# Hermes_v1.net
KiCad netlist of a schematic drawn in EAGLE
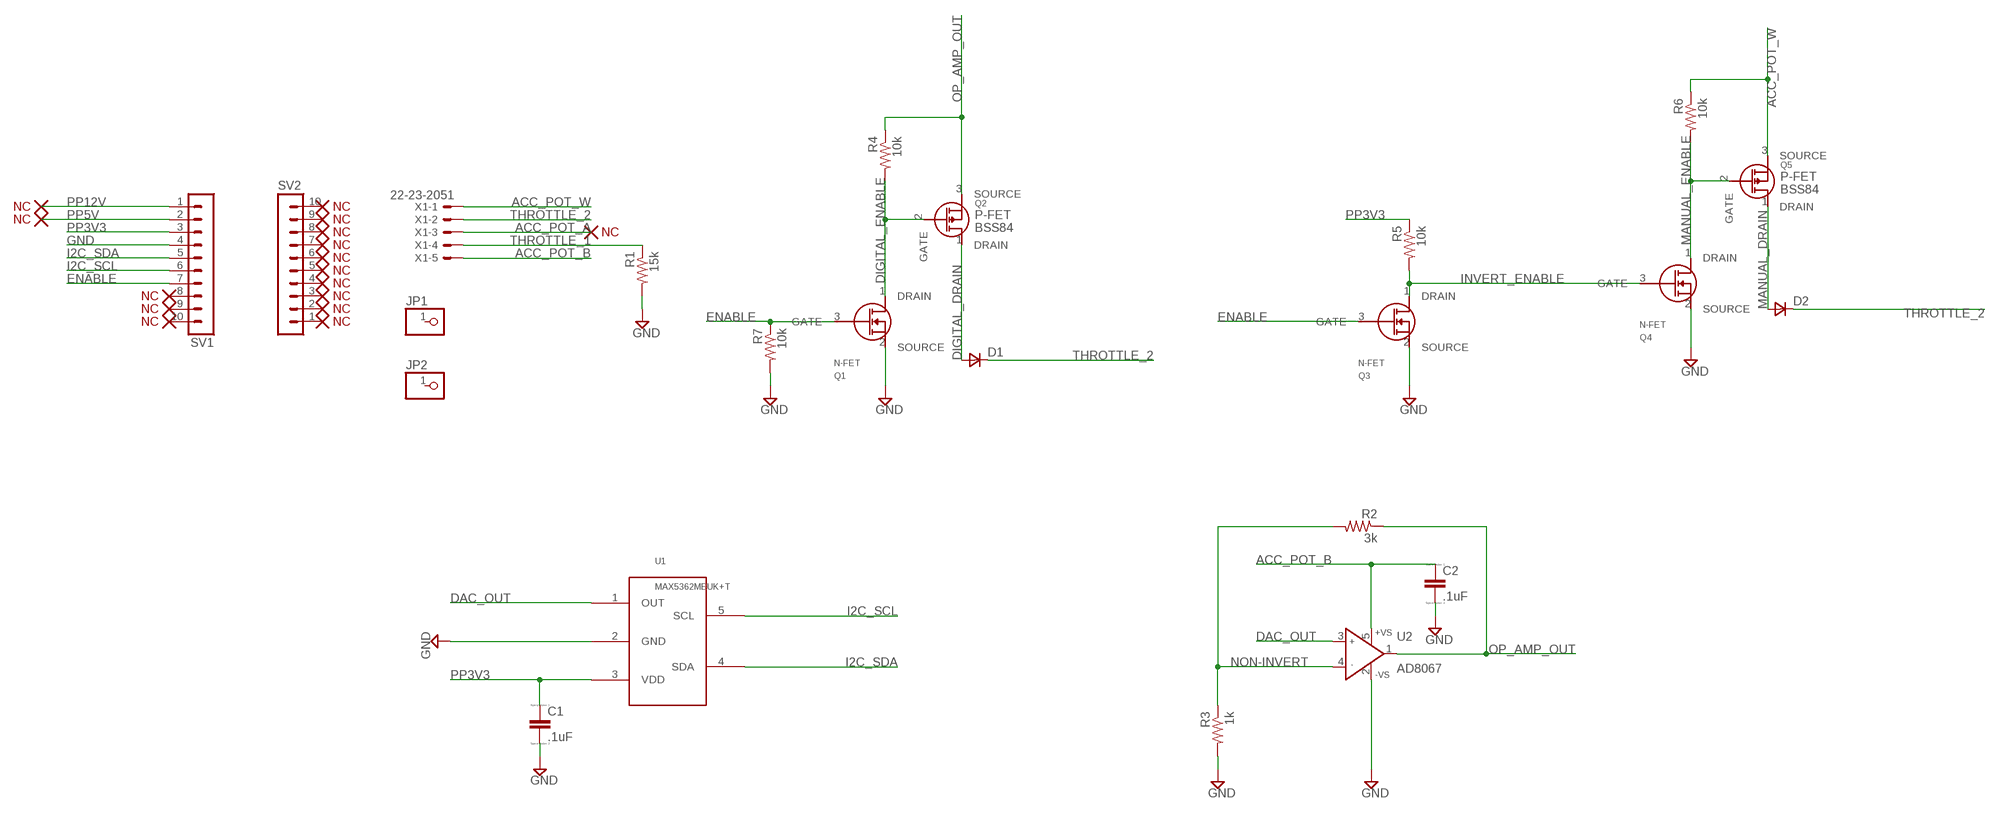
[diagram p0: schematic, sheet 1]

(export (version "E")
  (design (tool "Eeschema 10.0.6"))
  (components
    (comp (ref "C1")
      (value ".1uF")
      (footprint "eagle-import:C0402")
      (libsource (lib "eagle-import") (part "CC0402"))
    )
    (comp (ref "C2")
      (value ".1uF")
      (footprint "eagle-import:C0402")
      (libsource (lib "eagle-import") (part "CC0402"))
    )
    (comp (ref "D1")
      (value "DSOD323")
      (footprint "eagle-import:SOD323")
      (fields (field (name "MPN") "CDSOD323-T05C"))
      (libsource (lib "eagle-import") (part "DSOD323"))
    )
    (comp (ref "D2")
      (value "DSOD323")
      (footprint "eagle-import:SOD323")
      (fields (field (name "MPN") "CDSOD323-T05C"))
      (libsource (lib "eagle-import") (part "DSOD323"))
    )
    (comp (ref "JP1")
      (value "PINHD-1X1")
      (footprint "eagle-import:1X01")
      (libsource (lib "eagle-import") (part "PINHD-1X1"))
    )
    (comp (ref "JP2")
      (value "PINHD-1X1")
      (footprint "eagle-import:1X01")
      (libsource (lib "eagle-import") (part "PINHD-1X1"))
    )
    (comp (ref "Q1")
      (value "NMOSFET")
      (footprint "eagle-import:SOT-23")
      (libsource (lib "eagle-import") (part "NMOSFET"))
    )
    (comp (ref "Q2")
      (value "P-FET")
      (footprint "eagle-import:SOT-23")
      (libsource (lib "eagle-import") (part "P-FET"))
    )
    (comp (ref "Q3")
      (value "NMOSFET")
      (footprint "eagle-import:SOT-23")
      (libsource (lib "eagle-import") (part "NMOSFET"))
    )
    (comp (ref "Q4")
      (value "NMOSFET")
      (footprint "eagle-import:SOT-23")
      (libsource (lib "eagle-import") (part "NMOSFET"))
    )
    (comp (ref "Q5")
      (value "P-FET")
      (footprint "eagle-import:SOT-23")
      (libsource (lib "eagle-import") (part "P-FET"))
    )
    (comp (ref "R1")
      (value "15k")
      (footprint "eagle-import:R0603")
      (libsource (lib "eagle-import") (part "R-US_R0603"))
    )
    (comp (ref "R2")
      (value "3k")
      (footprint "eagle-import:R0603")
      (libsource (lib "eagle-import") (part "R-US_R0603"))
    )
    (comp (ref "R3")
      (value "1k")
      (footprint "eagle-import:R0603")
      (libsource (lib "eagle-import") (part "R-US_R0603"))
    )
    (comp (ref "R4")
      (value "10k")
      (footprint "eagle-import:R0603")
      (libsource (lib "eagle-import") (part "R-US_R0603"))
    )
    (comp (ref "R5")
      (value "10k")
      (footprint "eagle-import:R0603")
      (libsource (lib "eagle-import") (part "R-US_R0603"))
    )
    (comp (ref "R6")
      (value "10k")
      (footprint "eagle-import:R0603")
      (libsource (lib "eagle-import") (part "R-US_R0603"))
    )
    (comp (ref "R7")
      (value "10k")
      (footprint "eagle-import:R0603")
      (libsource (lib "eagle-import") (part "R-US_R0603"))
    )
    (comp (ref "SV1")
      (value "MA10-1")
      (footprint "eagle-import:MA10-1")
      (libsource (lib "eagle-import") (part "MA10-1"))
    )
    (comp (ref "SV2")
      (value "MA10-1")
      (footprint "eagle-import:MA10-1")
      (libsource (lib "eagle-import") (part "MA10-1"))
    )
    (comp (ref "U1")
      (value "DAC")
      (footprint "eagle-import:SOT23-5")
      (libsource (lib "eagle-import") (part "DAC"))
    )
    (comp (ref "U2")
      (value "AD8067")
      (footprint "eagle-import:SOT23-5")
      (fields (field (name "MF") "ALTERA CORPORATION") (field (name "MPN") "AD8067ARTZ-REEL7"))
      (libsource (lib "eagle-import") (part "AD8067"))
    )
    (comp (ref "X1")
      (value "22-23-2051")
      (footprint "eagle-import:22-23-2051")
      (fields (field (name "MF") "MOLEX"))
      (libsource (lib "eagle-import") (part "22-23-2051"))
    )
  )
  (nets
    (net (code "1") (name "/ACC_POT_A") (class "Default")
      (node (ref "X1") (pin "3") (pinfunction "S_3") (pintype "passive"))
    )
    (net (code "2") (name "/ACC_POT_B") (class "Default")
      (node (ref "C2") (pin "1") (pinfunction "1_1") (pintype "passive"))
      (node (ref "U2") (pin "5") (pinfunction "+VS_5") (pintype "input"))
      (node (ref "X1") (pin "5") (pinfunction "S_5") (pintype "passive"))
    )
    (net (code "3") (name "/ACC_POT_W") (class "Default")
      (node (ref "Q5") (pin "3") (pinfunction "SOURCE_3") (pintype "bidirectional"))
      (node (ref "R6") (pin "1") (pinfunction "1_1") (pintype "passive"))
      (node (ref "X1") (pin "1") (pinfunction "S_1") (pintype "passive"))
    )
    (net (code "4") (name "/DAC_OUT") (class "Default")
      (node (ref "U1") (pin "1") (pinfunction "OUT_1") (pintype "bidirectional"))
      (node (ref "U2") (pin "3") (pinfunction "IN+_3") (pintype "input"))
    )
    (net (code "5") (name "/DIGITAL_DRAIN") (class "Default")
      (node (ref "D1") (pin "2") (pinfunction "A_2") (pintype "passive"))
      (node (ref "Q2") (pin "1") (pinfunction "DRAIN_1") (pintype "bidirectional"))
    )
    (net (code "6") (name "/DIGITAL_ENABLE") (class "Default")
      (node (ref "Q1") (pin "1") (pinfunction "DRAIN_1") (pintype "bidirectional"))
      (node (ref "Q2") (pin "2") (pinfunction "GATE_2") (pintype "bidirectional"))
      (node (ref "R4") (pin "2") (pinfunction "2_2") (pintype "passive"))
    )
    (net (code "7") (name "/ENABLE") (class "Default")
      (node (ref "Q1") (pin "3") (pinfunction "GATE_3") (pintype "bidirectional"))
      (node (ref "Q3") (pin "3") (pinfunction "GATE_3") (pintype "bidirectional"))
      (node (ref "R7") (pin "1") (pinfunction "1_1") (pintype "passive"))
      (node (ref "SV1") (pin "7") (pinfunction "7_7") (pintype "passive"))
    )
    (net (code "8") (name "/I2C_SCL") (class "Default")
      (node (ref "SV1") (pin "6") (pinfunction "6_6") (pintype "passive"))
      (node (ref "U1") (pin "5") (pinfunction "SCL_5") (pintype "bidirectional"))
    )
    (net (code "9") (name "/I2C_SDA") (class "Default")
      (node (ref "SV1") (pin "5") (pinfunction "5_5") (pintype "passive"))
      (node (ref "U1") (pin "4") (pinfunction "SDA_4") (pintype "bidirectional"))
    )
    (net (code "10") (name "/INVERT_ENABLE") (class "Default")
      (node (ref "Q3") (pin "1") (pinfunction "DRAIN_1") (pintype "bidirectional"))
      (node (ref "Q4") (pin "3") (pinfunction "GATE_3") (pintype "bidirectional"))
      (node (ref "R5") (pin "2") (pinfunction "2_2") (pintype "passive"))
    )
    (net (code "11") (name "/MANUAL_DRAIN") (class "Default")
      (node (ref "D2") (pin "2") (pinfunction "A_2") (pintype "passive"))
      (node (ref "Q5") (pin "1") (pinfunction "DRAIN_1") (pintype "bidirectional"))
    )
    (net (code "12") (name "/MANUAL_ENABLE") (class "Default")
      (node (ref "Q4") (pin "1") (pinfunction "DRAIN_1") (pintype "bidirectional"))
      (node (ref "Q5") (pin "2") (pinfunction "GATE_2") (pintype "bidirectional"))
      (node (ref "R6") (pin "2") (pinfunction "2_2") (pintype "passive"))
    )
    (net (code "13") (name "/NON-INVERT") (class "Default")
      (node (ref "R2") (pin "2") (pinfunction "2_2") (pintype "passive"))
      (node (ref "R3") (pin "1") (pinfunction "1_1") (pintype "passive"))
      (node (ref "U2") (pin "4") (pinfunction "IN-_4") (pintype "input"))
    )
    (net (code "14") (name "/OP_AMP_OUT") (class "Default")
      (node (ref "Q2") (pin "3") (pinfunction "SOURCE_3") (pintype "bidirectional"))
      (node (ref "R2") (pin "1") (pinfunction "1_1") (pintype "passive"))
      (node (ref "R4") (pin "1") (pinfunction "1_1") (pintype "passive"))
      (node (ref "U2") (pin "1") (pinfunction "OUT_1") (pintype "output"))
    )
    (net (code "15") (name "/PP3V3") (class "Default")
      (node (ref "C1") (pin "1") (pinfunction "1_1") (pintype "passive"))
      (node (ref "R5") (pin "1") (pinfunction "1_1") (pintype "passive"))
      (node (ref "SV1") (pin "3") (pinfunction "3_3") (pintype "passive"))
      (node (ref "U1") (pin "3") (pinfunction "VDD_3") (pintype "bidirectional"))
    )
    (net (code "16") (name "/PP5V") (class "Default")
      (node (ref "SV1") (pin "2") (pinfunction "2_2") (pintype "passive"))
    )
    (net (code "17") (name "/PP12V") (class "Default")
      (node (ref "SV1") (pin "1") (pinfunction "1_1") (pintype "passive"))
    )
    (net (code "18") (name "/THROTTLE_1") (class "Default")
      (node (ref "R1") (pin "1") (pinfunction "1_1") (pintype "passive"))
      (node (ref "X1") (pin "4") (pinfunction "S_4") (pintype "passive"))
    )
    (net (code "19") (name "/THROTTLE_2") (class "Default")
      (node (ref "D1") (pin "1") (pinfunction "C_1") (pintype "passive"))
      (node (ref "D2") (pin "1") (pinfunction "C_1") (pintype "passive"))
      (node (ref "X1") (pin "2") (pinfunction "S_2") (pintype "passive"))
    )
    (net (code "20") (name "GND") (class "Default")
      (node (ref "C1") (pin "2") (pinfunction "2_2") (pintype "passive"))
      (node (ref "C2") (pin "2") (pinfunction "2_2") (pintype "passive"))
      (node (ref "Q1") (pin "2") (pinfunction "SOURCE_2") (pintype "bidirectional"))
      (node (ref "Q3") (pin "2") (pinfunction "SOURCE_2") (pintype "bidirectional"))
      (node (ref "Q4") (pin "2") (pinfunction "SOURCE_2") (pintype "bidirectional"))
      (node (ref "R1") (pin "2") (pinfunction "2_2") (pintype "passive"))
      (node (ref "R3") (pin "2") (pinfunction "2_2") (pintype "passive"))
      (node (ref "R7") (pin "2") (pinfunction "2_2") (pintype "passive"))
      (node (ref "SV1") (pin "4") (pinfunction "4_4") (pintype "passive"))
      (node (ref "U1") (pin "2") (pinfunction "GND_2") (pintype "bidirectional"))
      (node (ref "U2") (pin "2") (pinfunction "-VS_2") (pintype "input"))
    )
    (net (code "21") (name "unconnected-(JP1-Pad1)") (class "Default")
      (node (ref "JP1") (pin "1") (pinfunction "1_1") (pintype "passive"))
    )
    (net (code "22") (name "unconnected-(JP2-Pad1)") (class "Default")
      (node (ref "JP2") (pin "1") (pinfunction "1_1") (pintype "passive"))
    )
    (net (code "23") (name "unconnected-(SV1-Pad8)") (class "Default")
      (node (ref "SV1") (pin "8") (pinfunction "8_8") (pintype "passive"))
    )
    (net (code "24") (name "unconnected-(SV1-Pad9)") (class "Default")
      (node (ref "SV1") (pin "9") (pinfunction "9_9") (pintype "passive"))
    )
    (net (code "25") (name "unconnected-(SV1-Pad10)") (class "Default")
      (node (ref "SV1") (pin "10") (pinfunction "10_10") (pintype "passive"))
    )
    (net (code "26") (name "unconnected-(SV2-Pad1)") (class "Default")
      (node (ref "SV2") (pin "1") (pinfunction "1_1") (pintype "passive"))
    )
    (net (code "27") (name "unconnected-(SV2-Pad2)") (class "Default")
      (node (ref "SV2") (pin "2") (pinfunction "2_2") (pintype "passive"))
    )
    (net (code "28") (name "unconnected-(SV2-Pad3)") (class "Default")
      (node (ref "SV2") (pin "3") (pinfunction "3_3") (pintype "passive"))
    )
    (net (code "29") (name "unconnected-(SV2-Pad4)") (class "Default")
      (node (ref "SV2") (pin "4") (pinfunction "4_4") (pintype "passive"))
    )
    (net (code "30") (name "unconnected-(SV2-Pad5)") (class "Default")
      (node (ref "SV2") (pin "5") (pinfunction "5_5") (pintype "passive"))
    )
    (net (code "31") (name "unconnected-(SV2-Pad6)") (class "Default")
      (node (ref "SV2") (pin "6") (pinfunction "6_6") (pintype "passive"))
    )
    (net (code "32") (name "unconnected-(SV2-Pad7)") (class "Default")
      (node (ref "SV2") (pin "7") (pinfunction "7_7") (pintype "passive"))
    )
    (net (code "33") (name "unconnected-(SV2-Pad8)") (class "Default")
      (node (ref "SV2") (pin "8") (pinfunction "8_8") (pintype "passive"))
    )
    (net (code "34") (name "unconnected-(SV2-Pad9)") (class "Default")
      (node (ref "SV2") (pin "9") (pinfunction "9_9") (pintype "passive"))
    )
    (net (code "35") (name "unconnected-(SV2-Pad10)") (class "Default")
      (node (ref "SV2") (pin "10") (pinfunction "10_10") (pintype "passive"))
    )
  )
)
